# Tello_Power_PCB_XT30_Extension.net
KiCad netlist of a schematic drawn in EAGLE
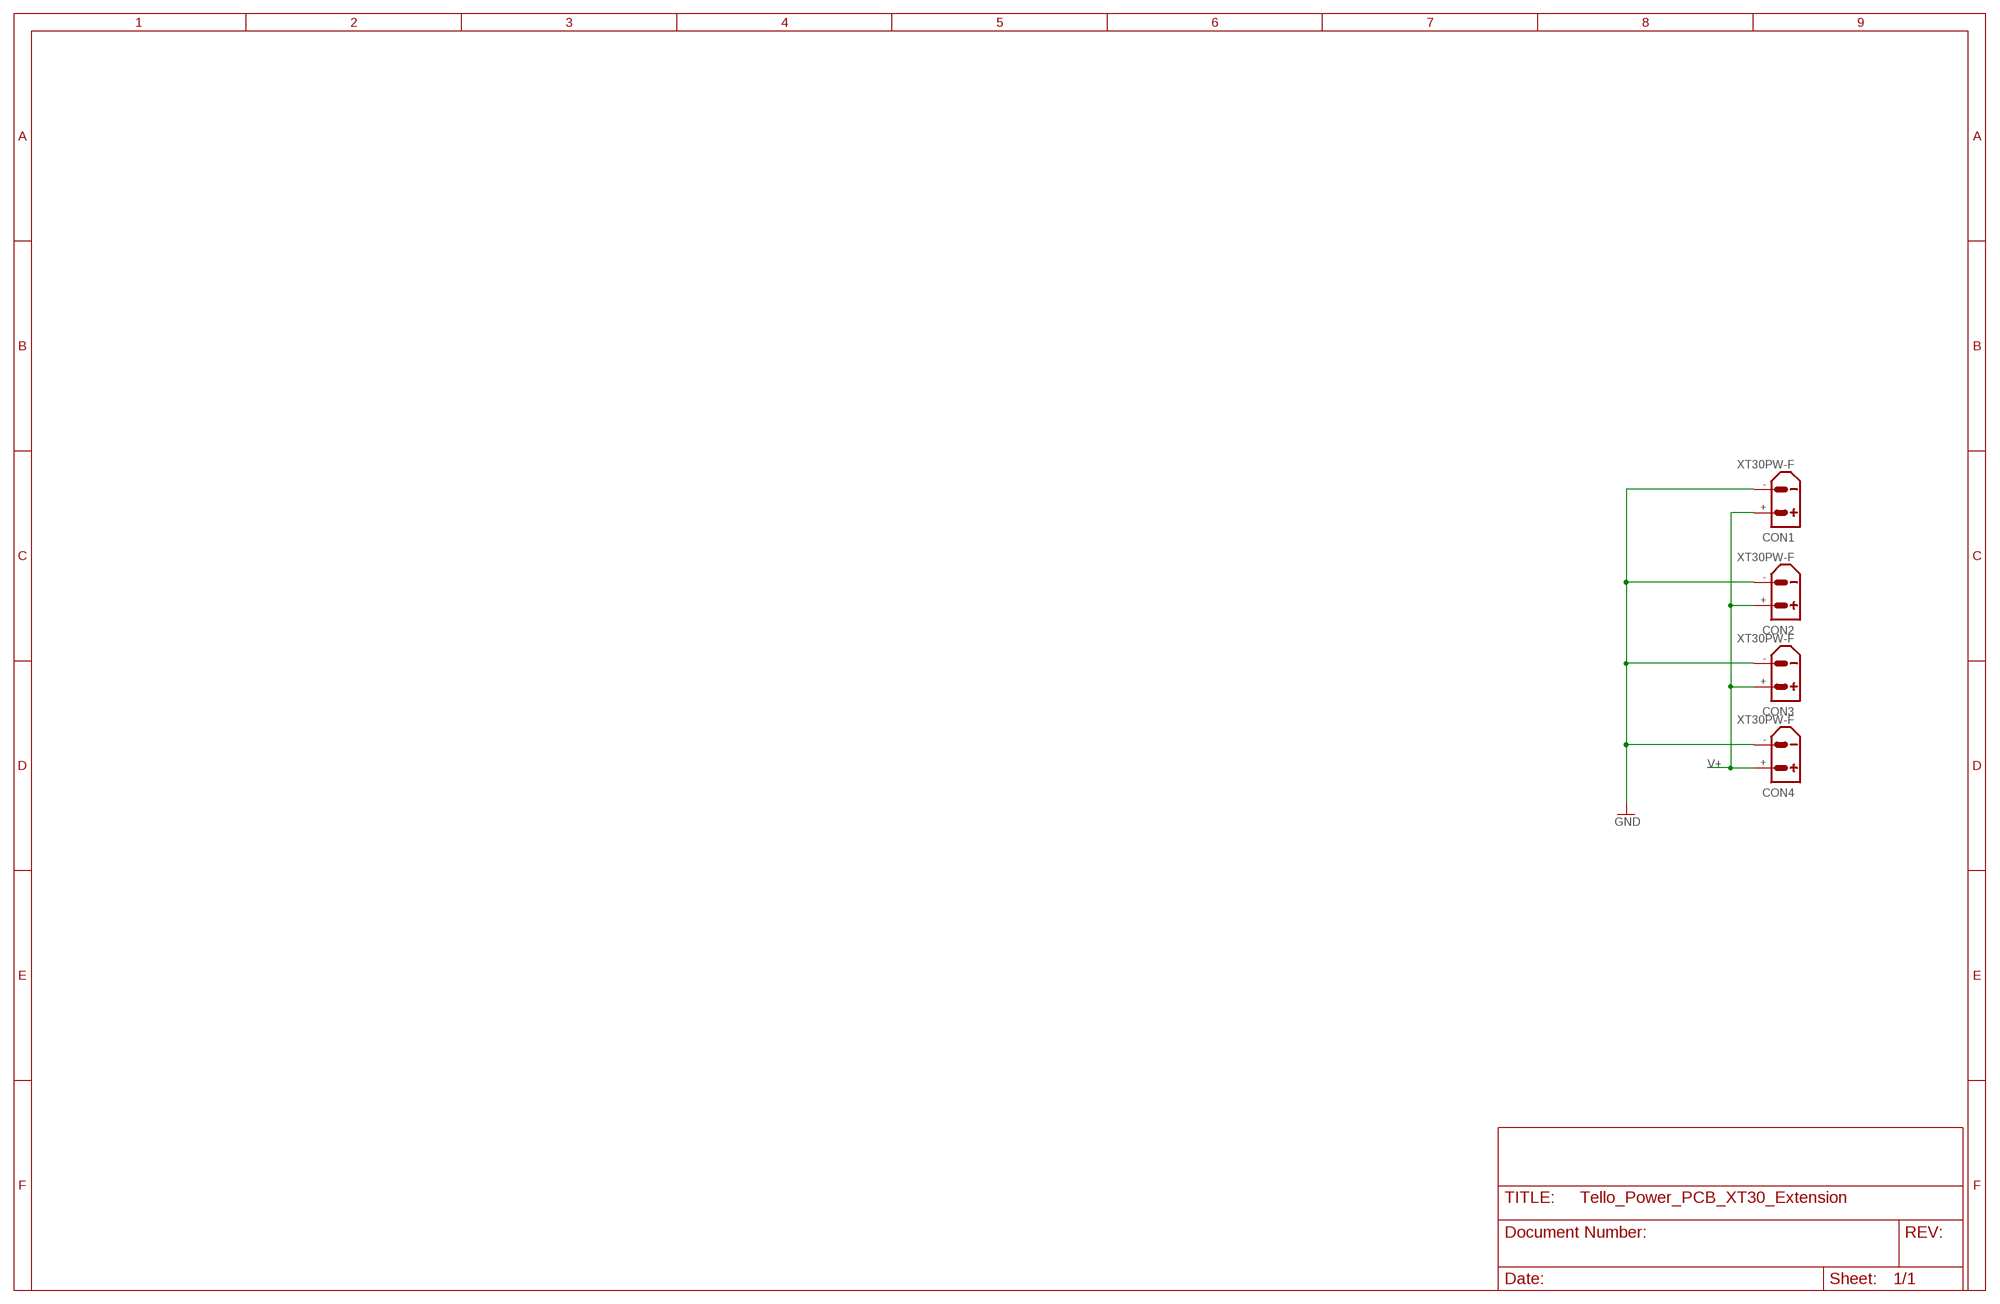
[diagram p0: schematic, sheet 1]

(export (version "E")
  (design (tool "Eeschema 10.0.6"))
  (components
    (comp (ref "CON1")
      (value "XT30PW-F")
      (footprint "eagle-import:XT30PW-F")
      (libsource (lib "eagle-import") (part "XT30PW-F"))
    )
    (comp (ref "CON2")
      (value "XT30PW-F")
      (footprint "eagle-import:XT30PW-F")
      (libsource (lib "eagle-import") (part "XT30PW-F"))
    )
    (comp (ref "CON3")
      (value "XT30PW-F")
      (footprint "eagle-import:XT30PW-F")
      (libsource (lib "eagle-import") (part "XT30PW-F"))
    )
    (comp (ref "CON4")
      (value "XT30PW-F")
      (footprint "eagle-import:XT30PW-F")
      (libsource (lib "eagle-import") (part "XT30PW-F"))
    )
  )
  (nets
    (net (code "1") (name "/V+") (class "Default")
      (node (ref "CON1") (pin "+") (pinfunction "+_+") (pintype "power_in"))
      (node (ref "CON2") (pin "+") (pinfunction "+_+") (pintype "power_in"))
      (node (ref "CON3") (pin "+") (pinfunction "+_+") (pintype "power_in"))
      (node (ref "CON4") (pin "+") (pinfunction "+_+") (pintype "power_in"))
    )
    (net (code "2") (name "GND") (class "Default")
      (node (ref "CON1") (pin "-") (pinfunction "-_-") (pintype "power_in"))
      (node (ref "CON2") (pin "-") (pinfunction "-_-") (pintype "power_in"))
      (node (ref "CON3") (pin "-") (pinfunction "-_-") (pintype "power_in"))
      (node (ref "CON4") (pin "-") (pinfunction "-_-") (pintype "power_in"))
    )
  )
)
